# Sheet1.net
KiCad netlist of a schematic drawn in Altium Designer
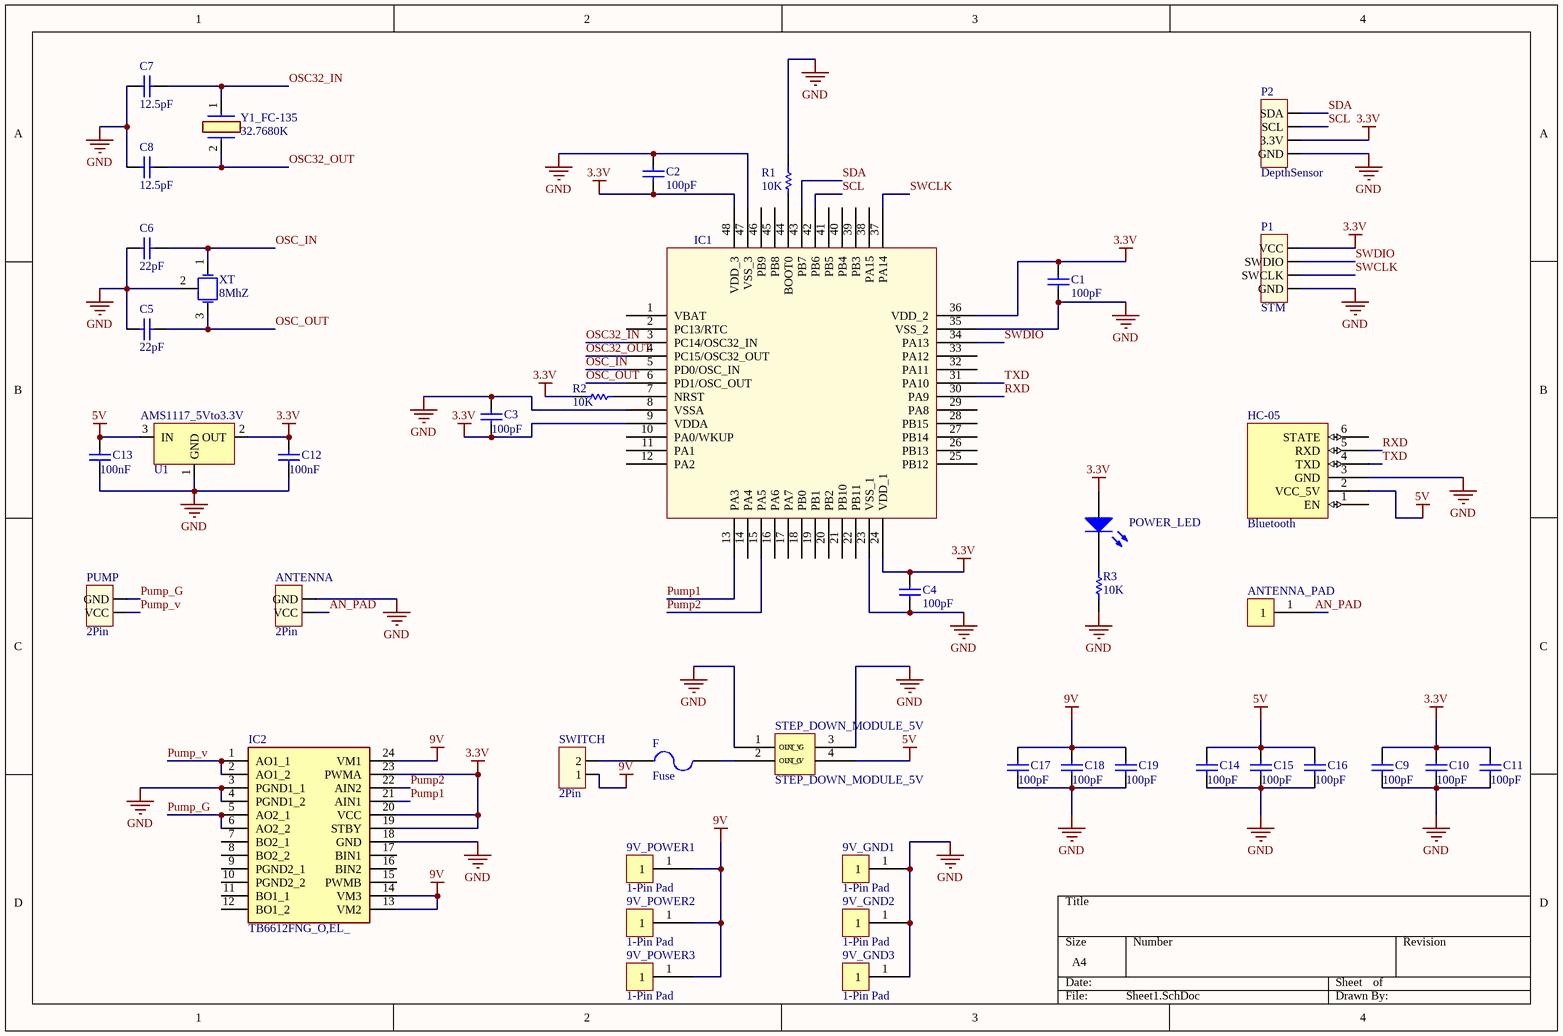
[diagram p0: Sheet1.SchDoc]

(export (version "E")
  (design (tool "Eeschema 10.0.6"))
  (components
    (comp (ref "9V_GND1")
      (value "1-Pin Pad")
      (footprint "1-Pin Pad")
      (libsource (lib "Connector") (part "1-Pin Pad"))
    )
    (comp (ref "9V_GND2")
      (value "1-Pin Pad")
      (footprint "1-Pin Pad")
      (libsource (lib "Connector") (part "1-Pin Pad"))
    )
    (comp (ref "9V_GND3")
      (value "1-Pin Pad")
      (footprint "1-Pin Pad")
      (libsource (lib "Connector") (part "1-Pin Pad"))
    )
    (comp (ref "9V_POWER1")
      (value "1-Pin Pad")
      (footprint "1-Pin Pad")
      (libsource (lib "Connector") (part "1-Pin Pad"))
    )
    (comp (ref "9V_POWER2")
      (value "1-Pin Pad")
      (footprint "1-Pin Pad")
      (libsource (lib "Connector") (part "1-Pin Pad"))
    )
    (comp (ref "9V_POWER3")
      (value "1-Pin Pad")
      (footprint "1-Pin Pad")
      (libsource (lib "Connector") (part "1-Pin Pad"))
    )
    (comp (ref "ANTENNA")
      (value "2Pin")
      (footprint "XH2.54-2pin")
      (libsource (lib "Connector") (part "2Pin"))
    )
    (comp (ref "ANTENNA_PAD")
      (value "1-Pin Pad")
      (footprint "1-Pin Pad")
      (libsource (lib "Connector") (part "1-Pin Pad"))
    )
    (comp (ref "C1") (value "100pF") (footprint "C0805") (libsource (lib "Passive Comp") (part "Cap")))
    (comp (ref "C2")
      (value "100pF")
      (footprint "Passive Comp:C0805")
      (libsource (lib "Passive Comp") (part "Cap"))
    )
    (comp (ref "C3") (value "100pF") (footprint "C0805") (libsource (lib "Passive Comp") (part "Cap")))
    (comp (ref "C4")
      (value "100pF")
      (footprint "Passive Comp:C0805")
      (libsource (lib "Passive Comp") (part "Cap"))
    )
    (comp (ref "C5")
      (value "22pF")
      (footprint "Passive Comp:C0805")
      (libsource (lib "Passive Comp") (part "Cap"))
    )
    (comp (ref "C6")
      (value "22pF")
      (footprint "Passive Comp:C0805")
      (libsource (lib "Passive Comp") (part "Cap"))
    )
    (comp (ref "C7")
      (value "12.5pF")
      (footprint "Passive Comp:C0805")
      (libsource (lib "Passive Comp") (part "Cap"))
    )
    (comp (ref "C8")
      (value "12.5pF")
      (footprint "Passive Comp:C0805")
      (libsource (lib "Passive Comp") (part "Cap"))
    )
    (comp (ref "C9")
      (value "100pF")
      (footprint "Passive Comp:C0805")
      (libsource (lib "Passive Comp") (part "Cap"))
    )
    (comp (ref "C10")
      (value "100pF")
      (footprint "Passive Comp:C0805")
      (libsource (lib "Passive Comp") (part "Cap"))
    )
    (comp (ref "C11")
      (value "100pF")
      (footprint "Passive Comp:C0805")
      (libsource (lib "Passive Comp") (part "Cap"))
    )
    (comp (ref "C12")
      (value "100nF")
      (footprint "Passive Comp:C0805")
      (libsource (lib "Passive Comp") (part "Cap"))
    )
    (comp (ref "C13")
      (value "100nF")
      (footprint "Passive Comp:C0805")
      (libsource (lib "Passive Comp") (part "Cap"))
    )
    (comp (ref "C14")
      (value "100pF")
      (footprint "Passive Comp:C0805")
      (libsource (lib "Passive Comp") (part "Cap"))
    )
    (comp (ref "C15")
      (value "100pF")
      (footprint "Passive Comp:C0805")
      (libsource (lib "Passive Comp") (part "Cap"))
    )
    (comp (ref "C16")
      (value "100pF")
      (footprint "Passive Comp:C0805")
      (libsource (lib "Passive Comp") (part "Cap"))
    )
    (comp (ref "C17")
      (value "100pF")
      (footprint "Passive Comp:C0805")
      (libsource (lib "Passive Comp") (part "Cap"))
    )
    (comp (ref "C18")
      (value "100pF")
      (footprint "Passive Comp:C0805")
      (libsource (lib "Passive Comp") (part "Cap"))
    )
    (comp (ref "C19")
      (value "100pF")
      (footprint "Passive Comp:C0805")
      (libsource (lib "Passive Comp") (part "Cap"))
    )
    (comp (ref "F")
      (value "Fuse")
      (footprint "FUSE-PPTC-30V - 5A")
      (description "PPTC")
      (libsource (lib "Passive Comp") (part "Fuse"))
    )
    (comp (ref "HC-05")
      (value "Bluetooth")
      (footprint "PcbLib1:hc-05")
      (libsource (lib "Schlib1") (part "HC-05"))
    )
    (comp (ref "IC1")
      (value "STM32F103C8T6")
      (footprint "LQFP48")
      (libsource (lib "STM32") (part "STM32F103C8T6"))
    )
    (comp (ref "IC2")
      (value "TB6612FNG_O,EL_")
      (footprint "SamacSys:SOP65P760X160-24N")
      (description "Integrated Circuit")
      (fields
        (field (name "MANUFACTURER_PART_NUMBER") "TB6612FNG(O,EL)")
        (field (name "MOUSER PART NUMBER") "757-TB6612FNG(O,EL)")
      )
      (libsource (lib "*") (part "TB6612FNG_O,EL_"))
    )
    (comp (ref "P1") (value "STM") (footprint "XH2.54-4pin") (libsource (lib "Connector") (part "4Pin")))
    (comp (ref "P2")
      (value "DepthSensor")
      (footprint "XH2.54-4pin")
      (libsource (lib "Connector") (part "4Pin"))
    )
    (comp (ref "POWER_LED") (value "LED") (footprint "LED:LED-0805") (libsource (lib "LED") (part "LED")))
    (comp (ref "PUMP") (value "2Pin") (footprint "XH2.54-2pin") (libsource (lib "Connector") (part "2Pin")))
    (comp (ref "R1") (value "10K") (footprint "R0805") (libsource (lib "Passive Comp") (part "Resistor_1")))
    (comp (ref "R2") (value "10K") (footprint "R0805") (libsource (lib "Passive Comp") (part "Resistor_1")))
    (comp (ref "R3") (value "10K") (footprint "R0805") (libsource (lib "Passive Comp") (part "Resistor_1")))
    (comp (ref "STEP_DOWN_MODULE_5V")
      (value "STEP_DOWN_MODULE_5V")
      (footprint "STEP_DOWN_MODULE_5V")
      (libsource (lib "Schlib1") (part "STEP_DOWN_MODULE_5V"))
    )
    (comp (ref "SWITCH") (value "2Pin") (footprint "XH2.54-2pin") (libsource (lib "Connector") (part "2Pin")))
    (comp (ref "U1")
      (value "AMS1117_5Vto3.3V")
      (footprint "AMS1117 - SOT-223")
      (libsource (lib "Converter") (part "AMS1117"))
    )
    (comp (ref "XT")
      (value "8MhZ")
      (footprint "3225-P")
      (libsource (lib "Passive Comp") (part "Passive Crystal"))
    )
    (comp (ref "Y1_FC-135")
      (value "32.7680K")
      (footprint "SamacSys:FC135327680KAAG0")
      (description "Crystal or Oscillator")
      (fields
        (field (name "MANUFACTURER_PART_NUMBER") "FC-135 32.7680KA-AG0")
        (field (name "MOUSER PART NUMBER") "732-FC135-32.76KAAG0")
      )
      (libsource (lib "*") (part "FC-135_32.7680KA-AG0"))
    )
  )
  (nets
    (net (code "1") (name "/AN_PAD") (class "Default")
      (node (ref "ANTENNA") (pin "1") (pinfunction "VCC_1") (pintype "passive"))
      (node (ref "ANTENNA_PAD") (pin "1") (pinfunction "1_1") (pintype "passive"))
    )
    (net (code "2") (name "/OSC32_IN") (class "Default")
      (node (ref "C7") (pin "2") (pinfunction "2_2") (pintype "passive"))
      (node (ref "IC1") (pin "3") (pinfunction "PC14/OSC32_IN_3") (pintype "passive"))
      (node (ref "Y1_FC-135") (pin "1") (pinfunction "CRYSTAL_1_1") (pintype "passive"))
    )
    (net (code "3") (name "/OSC32_OUT") (class "Default")
      (node (ref "C8") (pin "2") (pinfunction "2_2") (pintype "passive"))
      (node (ref "IC1") (pin "4") (pinfunction "PC15/OSC32_OUT_4") (pintype "passive"))
      (node (ref "Y1_FC-135") (pin "2") (pinfunction "CRYSTAL_2_2") (pintype "passive"))
    )
    (net (code "4") (name "/OSC_IN") (class "Default")
      (node (ref "C6") (pin "2") (pinfunction "2_2") (pintype "passive"))
      (node (ref "IC1") (pin "5") (pinfunction "PD0/OSC_IN_5") (pintype "passive"))
      (node (ref "XT") (pin "1") (pinfunction "OSC1_1") (pintype "passive"))
    )
    (net (code "5") (name "/OSC_OUT") (class "Default")
      (node (ref "C5") (pin "2") (pinfunction "2_2") (pintype "passive"))
      (node (ref "IC1") (pin "6") (pinfunction "PD1/OSC_OUT_6") (pintype "passive"))
      (node (ref "XT") (pin "3") (pinfunction "OSC2_3") (pintype "passive"))
    )
    (net (code "6") (name "/Pump1") (class "Default")
      (node (ref "IC1") (pin "13") (pinfunction "PA3_13") (pintype "passive"))
      (node (ref "IC2") (pin "21") (pinfunction "AIN1_21") (pintype "passive"))
    )
    (net (code "7") (name "/Pump2") (class "Default")
      (node (ref "IC1") (pin "15") (pinfunction "PA5_15") (pintype "passive"))
      (node (ref "IC2") (pin "22") (pinfunction "AIN2_22") (pintype "passive"))
    )
    (net (code "8") (name "/Pump_G") (class "Default")
      (node (ref "IC2") (pin "5") (pinfunction "AO2_1_5") (pintype "passive"))
      (node (ref "IC2") (pin "6") (pinfunction "AO2_2_6") (pintype "passive"))
      (node (ref "PUMP") (pin "2") (pinfunction "GND_2") (pintype "passive"))
    )
    (net (code "9") (name "/Pump_v") (class "Default")
      (node (ref "IC2") (pin "1") (pinfunction "AO1_1_1") (pintype "passive"))
      (node (ref "IC2") (pin "2") (pinfunction "AO1_2_2") (pintype "passive"))
      (node (ref "PUMP") (pin "1") (pinfunction "VCC_1") (pintype "passive"))
    )
    (net (code "10") (name "/RXD") (class "Default")
      (node (ref "HC-05") (pin "5") (pinfunction "RXD_5") (pintype "bidirectional"))
      (node (ref "IC1") (pin "30") (pinfunction "PA9_30") (pintype "passive"))
    )
    (net (code "11") (name "/SCL") (class "Default")
      (node (ref "IC1") (pin "42") (pinfunction "PB6_42") (pintype "passive"))
      (node (ref "P2") (pin "3") (pinfunction "SCL_3") (pintype "passive"))
    )
    (net (code "12") (name "/SDA") (class "Default")
      (node (ref "IC1") (pin "43") (pinfunction "PB7_43") (pintype "passive"))
      (node (ref "P2") (pin "4") (pinfunction "SDA_4") (pintype "passive"))
    )
    (net (code "13") (name "/SWCLK") (class "Default")
      (node (ref "IC1") (pin "37") (pinfunction "PA14_37") (pintype "passive"))
      (node (ref "P1") (pin "2") (pinfunction "3.3V_2") (pintype "passive"))
    )
    (net (code "14") (name "/SWDIO") (class "Default")
      (node (ref "IC1") (pin "34") (pinfunction "PA13_34") (pintype "passive"))
      (node (ref "P1") (pin "3") (pinfunction "SCL_3") (pintype "passive"))
    )
    (net (code "15") (name "/TXD") (class "Default")
      (node (ref "HC-05") (pin "4") (pinfunction "TXD_4") (pintype "bidirectional"))
      (node (ref "IC1") (pin "31") (pinfunction "PA10_31") (pintype "passive"))
    )
    (net (code "16") (name "3.3V") (class "Default")
      (node (ref "C1") (pin "2") (pinfunction "2_2") (pintype "passive"))
      (node (ref "C10") (pin "2") (pinfunction "2_2") (pintype "passive"))
      (node (ref "C11") (pin "2") (pinfunction "2_2") (pintype "passive"))
      (node (ref "C12") (pin "2") (pinfunction "2_2") (pintype "passive"))
      (node (ref "C2") (pin "1") (pinfunction "1_1") (pintype "passive"))
      (node (ref "C3") (pin "1") (pinfunction "1_1") (pintype "passive"))
      (node (ref "C4") (pin "2") (pinfunction "2_2") (pintype "passive"))
      (node (ref "C9") (pin "2") (pinfunction "2_2") (pintype "passive"))
      (node (ref "IC1") (pin "24") (pinfunction "VDD_1_24") (pintype "passive"))
      (node (ref "IC1") (pin "36") (pinfunction "VDD_2_36") (pintype "passive"))
      (node (ref "IC1") (pin "48") (pinfunction "VDD_3_48") (pintype "passive"))
      (node (ref "IC1") (pin "9") (pinfunction "VDDA_9") (pintype "passive"))
      (node (ref "IC2") (pin "19") (pinfunction "STBY_19") (pintype "passive"))
      (node (ref "IC2") (pin "20") (pinfunction "VCC_20") (pintype "passive"))
      (node (ref "IC2") (pin "23") (pinfunction "PWMA_23") (pintype "passive"))
      (node (ref "P1") (pin "4") (pinfunction "SDA_4") (pintype "passive"))
      (node (ref "P2") (pin "2") (pinfunction "3.3V_2") (pintype "passive"))
      (node (ref "POWER_LED") (pin "1") (pinfunction "A_1") (pintype "passive"))
      (node (ref "R2") (pin "1") (pinfunction "1_1") (pintype "passive"))
      (node (ref "U1") (pin "2") (pinfunction "OUT_2") (pintype "passive"))
    )
    (net (code "17") (name "5V") (class "Default")
      (node (ref "C13") (pin "2") (pinfunction "2_2") (pintype "passive"))
      (node (ref "C14") (pin "2") (pinfunction "2_2") (pintype "passive"))
      (node (ref "C15") (pin "2") (pinfunction "2_2") (pintype "passive"))
      (node (ref "C16") (pin "2") (pinfunction "2_2") (pintype "passive"))
      (node (ref "HC-05") (pin "2") (pinfunction "VCC_5V_2") (pintype "power_in"))
      (node (ref "STEP_DOWN_MODULE_5V") (pin "4") (pinfunction "OUT_V_4") (pintype "passive"))
      (node (ref "U1") (pin "3") (pinfunction "IN_3") (pintype "passive"))
    )
    (net (code "18") (name "9V") (class "Default")
      (node (ref "9V_POWER1") (pin "1") (pinfunction "1_1") (pintype "passive"))
      (node (ref "9V_POWER2") (pin "1") (pinfunction "1_1") (pintype "passive"))
      (node (ref "9V_POWER3") (pin "1") (pinfunction "1_1") (pintype "passive"))
      (node (ref "C17") (pin "2") (pinfunction "2_2") (pintype "passive"))
      (node (ref "C18") (pin "2") (pinfunction "2_2") (pintype "passive"))
      (node (ref "C19") (pin "2") (pinfunction "2_2") (pintype "passive"))
      (node (ref "IC2") (pin "13") (pinfunction "VM2_13") (pintype "passive"))
      (node (ref "IC2") (pin "14") (pinfunction "VM3_14") (pintype "passive"))
      (node (ref "IC2") (pin "24") (pinfunction "VM1_24") (pintype "passive"))
      (node (ref "SWITCH") (pin "1") (pinfunction "VCC_1") (pintype "passive"))
    )
    (net (code "19") (name "GND") (class "Default")
      (node (ref "9V_GND1") (pin "1") (pinfunction "1_1") (pintype "passive"))
      (node (ref "9V_GND2") (pin "1") (pinfunction "1_1") (pintype "passive"))
      (node (ref "9V_GND3") (pin "1") (pinfunction "1_1") (pintype "passive"))
      (node (ref "ANTENNA") (pin "2") (pinfunction "GND_2") (pintype "passive"))
      (node (ref "C1") (pin "1") (pinfunction "1_1") (pintype "passive"))
      (node (ref "C10") (pin "1") (pinfunction "1_1") (pintype "passive"))
      (node (ref "C11") (pin "1") (pinfunction "1_1") (pintype "passive"))
      (node (ref "C12") (pin "1") (pinfunction "1_1") (pintype "passive"))
      (node (ref "C13") (pin "1") (pinfunction "1_1") (pintype "passive"))
      (node (ref "C14") (pin "1") (pinfunction "1_1") (pintype "passive"))
      (node (ref "C15") (pin "1") (pinfunction "1_1") (pintype "passive"))
      (node (ref "C16") (pin "1") (pinfunction "1_1") (pintype "passive"))
      (node (ref "C17") (pin "1") (pinfunction "1_1") (pintype "passive"))
      (node (ref "C18") (pin "1") (pinfunction "1_1") (pintype "passive"))
      (node (ref "C19") (pin "1") (pinfunction "1_1") (pintype "passive"))
      (node (ref "C2") (pin "2") (pinfunction "2_2") (pintype "passive"))
      (node (ref "C3") (pin "2") (pinfunction "2_2") (pintype "passive"))
      (node (ref "C4") (pin "1") (pinfunction "1_1") (pintype "passive"))
      (node (ref "C5") (pin "1") (pinfunction "1_1") (pintype "passive"))
      (node (ref "C6") (pin "1") (pinfunction "1_1") (pintype "passive"))
      (node (ref "C7") (pin "1") (pinfunction "1_1") (pintype "passive"))
      (node (ref "C8") (pin "1") (pinfunction "1_1") (pintype "passive"))
      (node (ref "C9") (pin "1") (pinfunction "1_1") (pintype "passive"))
      (node (ref "HC-05") (pin "3") (pinfunction "GND_3") (pintype "passive"))
      (node (ref "IC1") (pin "23") (pinfunction "VSS_1_23") (pintype "passive"))
      (node (ref "IC1") (pin "35") (pinfunction "VSS_2_35") (pintype "passive"))
      (node (ref "IC1") (pin "47") (pinfunction "VSS_3_47") (pintype "passive"))
      (node (ref "IC1") (pin "8") (pinfunction "VSSA_8") (pintype "passive"))
      (node (ref "IC2") (pin "18") (pinfunction "GND_18") (pintype "passive"))
      (node (ref "IC2") (pin "3") (pinfunction "PGND1_1_3") (pintype "passive"))
      (node (ref "IC2") (pin "4") (pinfunction "PGND1_2_4") (pintype "passive"))
      (node (ref "P1") (pin "1") (pinfunction "GND_1") (pintype "passive"))
      (node (ref "P2") (pin "1") (pinfunction "GND_1") (pintype "passive"))
      (node (ref "R1") (pin "2") (pinfunction "2_2") (pintype "passive"))
      (node (ref "R3") (pin "1") (pinfunction "1_1") (pintype "passive"))
      (node (ref "STEP_DOWN_MODULE_5V") (pin "1") (pinfunction "IN_V_1") (pintype "power_in"))
      (node (ref "STEP_DOWN_MODULE_5V") (pin "3") (pinfunction "OUT_G_3") (pintype "power_in"))
      (node (ref "U1") (pin "1") (pinfunction "GND_1") (pintype "passive"))
      (node (ref "XT") (pin "2") (pinfunction "2_2") (pintype "passive"))
    )
    (net (code "20") (name "Net-(IC1-BOOT0)") (class "Default")
      (node (ref "IC1") (pin "44") (pinfunction "BOOT0_44") (pintype "passive"))
      (node (ref "R1") (pin "1") (pinfunction "1_1") (pintype "passive"))
    )
    (net (code "21") (name "Net-(IC1-NRST)") (class "Default")
      (node (ref "IC1") (pin "7") (pinfunction "NRST_7") (pintype "passive"))
      (node (ref "R2") (pin "2") (pinfunction "2_2") (pintype "passive"))
    )
    (net (code "22") (name "Net-(POWER_LED-K)") (class "Default")
      (node (ref "POWER_LED") (pin "2") (pinfunction "K_2") (pintype "passive"))
      (node (ref "R3") (pin "2") (pinfunction "2_2") (pintype "passive"))
    )
    (net (code "23") (name "Net-(STEP_DOWN_MODULE_5V-IN_G)") (class "Default")
      (node (ref "F") (pin "2") (pinfunction "2_2") (pintype "passive"))
      (node (ref "STEP_DOWN_MODULE_5V") (pin "2") (pinfunction "IN_G_2") (pintype "passive"))
    )
    (net (code "24") (name "Net-(SWITCH-GND)") (class "Default")
      (node (ref "F") (pin "1") (pinfunction "1_1") (pintype "passive"))
      (node (ref "SWITCH") (pin "2") (pinfunction "GND_2") (pintype "passive"))
    )
    (net (code "25") (name "unconnected-(HC-05-EN-Pad1)") (class "Default")
      (node (ref "HC-05") (pin "1") (pinfunction "EN_1") (pintype "bidirectional"))
    )
    (net (code "26") (name "unconnected-(HC-05-STATE-Pad6)") (class "Default")
      (node (ref "HC-05") (pin "6") (pinfunction "STATE_6") (pintype "bidirectional"))
    )
    (net (code "27") (name "unconnected-(IC1-PA0{slash}WKUP-Pad10)") (class "Default")
      (node (ref "IC1") (pin "10") (pinfunction "PA0/WKUP_10") (pintype "passive"))
    )
    (net (code "28") (name "unconnected-(IC1-PA1-Pad11)") (class "Default")
      (node (ref "IC1") (pin "11") (pinfunction "PA1_11") (pintype "passive"))
    )
    (net (code "29") (name "unconnected-(IC1-PA2-Pad12)") (class "Default")
      (node (ref "IC1") (pin "12") (pinfunction "PA2_12") (pintype "passive"))
    )
    (net (code "30") (name "unconnected-(IC1-PA4-Pad14)") (class "Default")
      (node (ref "IC1") (pin "14") (pinfunction "PA4_14") (pintype "passive"))
    )
    (net (code "31") (name "unconnected-(IC1-PA6-Pad16)") (class "Default")
      (node (ref "IC1") (pin "16") (pinfunction "PA6_16") (pintype "passive"))
    )
    (net (code "32") (name "unconnected-(IC1-PA7-Pad17)") (class "Default")
      (node (ref "IC1") (pin "17") (pinfunction "PA7_17") (pintype "passive"))
    )
    (net (code "33") (name "unconnected-(IC1-PA8-Pad29)") (class "Default")
      (node (ref "IC1") (pin "29") (pinfunction "PA8_29") (pintype "passive"))
    )
    (net (code "34") (name "unconnected-(IC1-PA11-Pad32)") (class "Default")
      (node (ref "IC1") (pin "32") (pinfunction "PA11_32") (pintype "passive"))
    )
    (net (code "35") (name "unconnected-(IC1-PA12-Pad33)") (class "Default")
      (node (ref "IC1") (pin "33") (pinfunction "PA12_33") (pintype "passive"))
    )
    (net (code "36") (name "unconnected-(IC1-PA15-Pad38)") (class "Default")
      (node (ref "IC1") (pin "38") (pinfunction "PA15_38") (pintype "passive"))
    )
    (net (code "37") (name "unconnected-(IC1-PB0-Pad18)") (class "Default")
      (node (ref "IC1") (pin "18") (pinfunction "PB0_18") (pintype "passive"))
    )
    (net (code "38") (name "unconnected-(IC1-PB1-Pad19)") (class "Default")
      (node (ref "IC1") (pin "19") (pinfunction "PB1_19") (pintype "passive"))
    )
    (net (code "39") (name "unconnected-(IC1-PB2-Pad20)") (class "Default")
      (node (ref "IC1") (pin "20") (pinfunction "PB2_20") (pintype "passive"))
    )
    (net (code "40") (name "unconnected-(IC1-PB3-Pad39)") (class "Default")
      (node (ref "IC1") (pin "39") (pinfunction "PB3_39") (pintype "passive"))
    )
    (net (code "41") (name "unconnected-(IC1-PB4-Pad40)") (class "Default")
      (node (ref "IC1") (pin "40") (pinfunction "PB4_40") (pintype "passive"))
    )
    (net (code "42") (name "unconnected-(IC1-PB5-Pad41)") (class "Default")
      (node (ref "IC1") (pin "41") (pinfunction "PB5_41") (pintype "passive"))
    )
    (net (code "43") (name "unconnected-(IC1-PB8-Pad45)") (class "Default")
      (node (ref "IC1") (pin "45") (pinfunction "PB8_45") (pintype "passive"))
    )
    (net (code "44") (name "unconnected-(IC1-PB9-Pad46)") (class "Default")
      (node (ref "IC1") (pin "46") (pinfunction "PB9_46") (pintype "passive"))
    )
    (net (code "45") (name "unconnected-(IC1-PB10-Pad21)") (class "Default")
      (node (ref "IC1") (pin "21") (pinfunction "PB10_21") (pintype "passive"))
    )
    (net (code "46") (name "unconnected-(IC1-PB11-Pad22)") (class "Default")
      (node (ref "IC1") (pin "22") (pinfunction "PB11_22") (pintype "passive"))
    )
    (net (code "47") (name "unconnected-(IC1-PB12-Pad25)") (class "Default")
      (node (ref "IC1") (pin "25") (pinfunction "PB12_25") (pintype "passive"))
    )
    (net (code "48") (name "unconnected-(IC1-PB13-Pad26)") (class "Default")
      (node (ref "IC1") (pin "26") (pinfunction "PB13_26") (pintype "passive"))
    )
    (net (code "49") (name "unconnected-(IC1-PB14-Pad27)") (class "Default")
      (node (ref "IC1") (pin "27") (pinfunction "PB14_27") (pintype "passive"))
    )
    (net (code "50") (name "unconnected-(IC1-PB15-Pad28)") (class "Default")
      (node (ref "IC1") (pin "28") (pinfunction "PB15_28") (pintype "passive"))
    )
    (net (code "51") (name "unconnected-(IC1-PC13{slash}RTC-Pad2)") (class "Default")
      (node (ref "IC1") (pin "2") (pinfunction "PC13/RTC_2") (pintype "passive"))
    )
    (net (code "52") (name "unconnected-(IC1-VBAT-Pad1)") (class "Default")
      (node (ref "IC1") (pin "1") (pinfunction "VBAT_1") (pintype "passive"))
    )
    (net (code "53") (name "unconnected-(IC2-BIN1-Pad17)") (class "Default")
      (node (ref "IC2") (pin "17") (pinfunction "BIN1_17") (pintype "passive"))
    )
    (net (code "54") (name "unconnected-(IC2-BIN2-Pad16)") (class "Default")
      (node (ref "IC2") (pin "16") (pinfunction "BIN2_16") (pintype "passive"))
    )
    (net (code "55") (name "unconnected-(IC2-BO1_1-Pad11)") (class "Default")
      (node (ref "IC2") (pin "11") (pinfunction "BO1_1_11") (pintype "passive"))
    )
    (net (code "56") (name "unconnected-(IC2-BO1_2-Pad12)") (class "Default")
      (node (ref "IC2") (pin "12") (pinfunction "BO1_2_12") (pintype "passive"))
    )
    (net (code "57") (name "unconnected-(IC2-BO2_1-Pad7)") (class "Default")
      (node (ref "IC2") (pin "7") (pinfunction "BO2_1_7") (pintype "passive"))
    )
    (net (code "58") (name "unconnected-(IC2-BO2_2-Pad8)") (class "Default")
      (node (ref "IC2") (pin "8") (pinfunction "BO2_2_8") (pintype "passive"))
    )
    (net (code "59") (name "unconnected-(IC2-PGND2_1-Pad9)") (class "Default")
      (node (ref "IC2") (pin "9") (pinfunction "PGND2_1_9") (pintype "passive"))
    )
    (net (code "60") (name "unconnected-(IC2-PGND2_2-Pad10)") (class "Default")
      (node (ref "IC2") (pin "10") (pinfunction "PGND2_2_10") (pintype "passive"))
    )
    (net (code "61") (name "unconnected-(IC2-PWMB-Pad15)") (class "Default")
      (node (ref "IC2") (pin "15") (pinfunction "PWMB_15") (pintype "passive"))
    )
  )
)
